# desk_winder.net
KiCad netlist of a schematic drawn in EAGLE
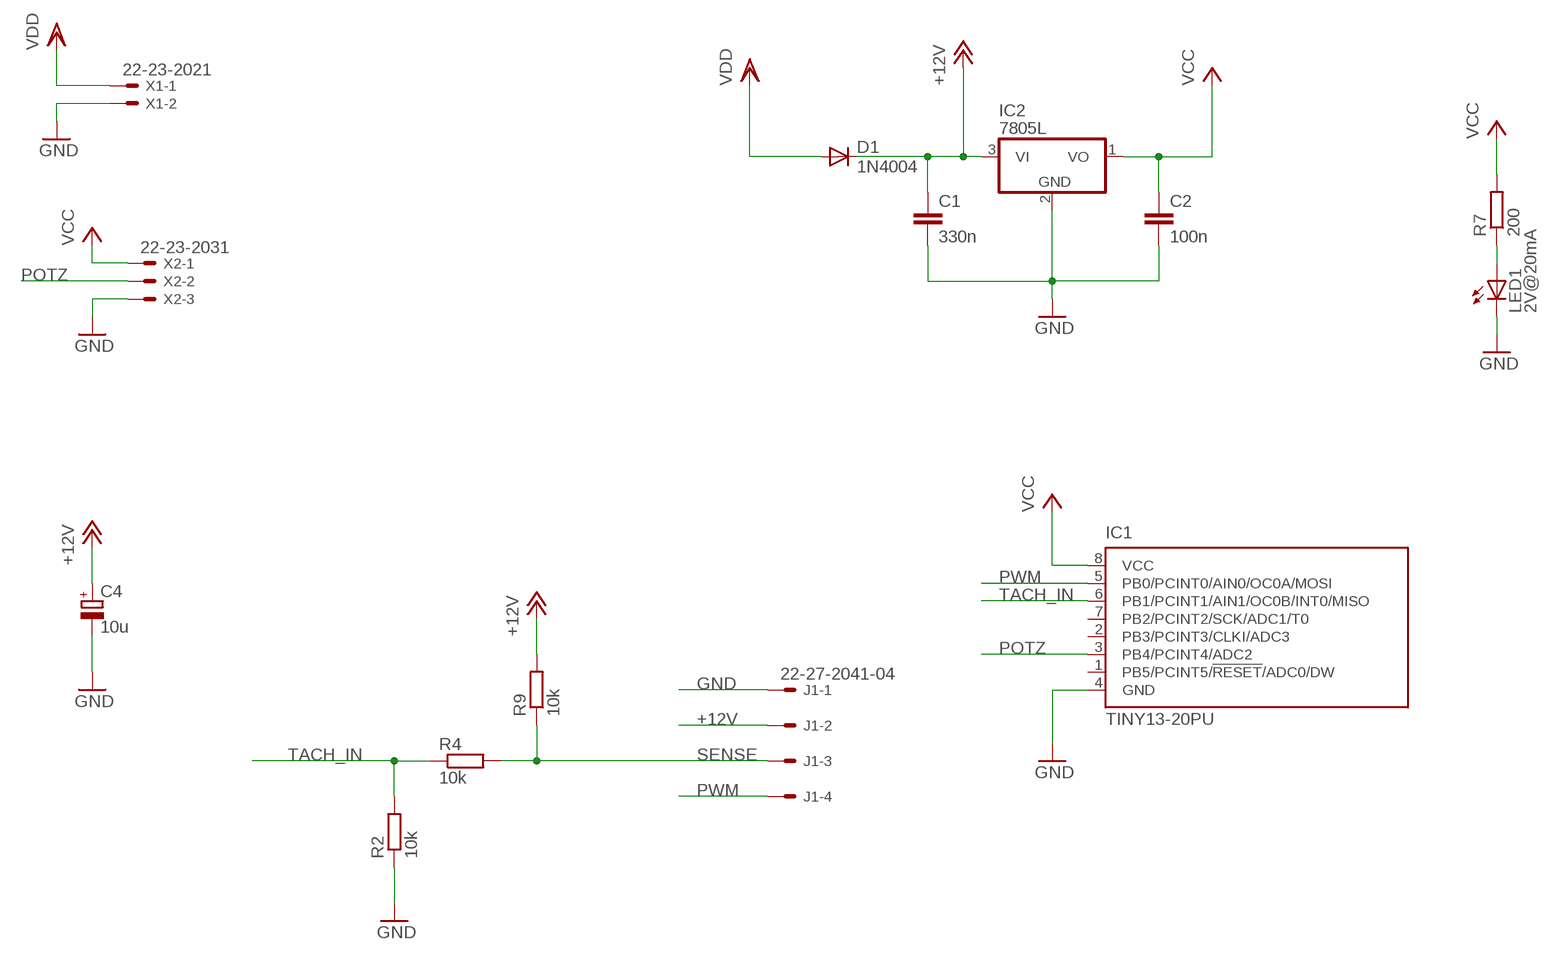
[diagram p0: schematic, sheet 1]

(export (version "E")
  (design (tool "Eeschema 10.0.6"))
  (components
    (comp (ref "C1")
      (value "330n")
      (footprint "eagle-import:C050-025X075")
      (libsource (lib "eagle-import") (part "C-EU050-025X075"))
    )
    (comp (ref "C2")
      (value "100n")
      (footprint "eagle-import:C050-025X075")
      (libsource (lib "eagle-import") (part "C-EU050-025X075"))
    )
    (comp (ref "C4")
      (value "10u")
      (footprint "eagle-import:E2,5-6")
      (libsource (lib "eagle-import") (part "CPOL-EUE2.5-6"))
    )
    (comp (ref "D1")
      (value "1N4004")
      (footprint "eagle-import:DO41-10")
      (libsource (lib "eagle-import") (part "1N4004"))
    )
    (comp (ref "IC1")
      (value "TINY13-20PU")
      (footprint "eagle-import:DIL08")
      (fields (field (name "MPN") "ATTINY13-20PU"))
      (libsource (lib "eagle-import") (part "TINY13PU-20"))
    )
    (comp (ref "IC2")
      (value "7805L")
      (footprint "eagle-import:TO92")
      (libsource (lib "eagle-import") (part "78L05"))
    )
    (comp (ref "J1")
      (value "22-27-2041-04")
      (footprint "eagle-import:6410-04")
      (libsource (lib "eagle-import") (part "22-?-0427-2041"))
    )
    (comp (ref "LED1")
      (value "2V@20mA")
      (footprint "eagle-import:LED5MM")
      (libsource (lib "eagle-import") (part "LED5MM"))
    )
    (comp (ref "R2")
      (value "10k")
      (footprint "eagle-import:0207_12")
      (libsource (lib "eagle-import") (part "R-EU_0207/12"))
    )
    (comp (ref "R4")
      (value "10k")
      (footprint "eagle-import:0207_12")
      (libsource (lib "eagle-import") (part "R-EU_0207/12"))
    )
    (comp (ref "R7")
      (value "200")
      (footprint "eagle-import:0207_12")
      (libsource (lib "eagle-import") (part "R-EU_0207/12"))
    )
    (comp (ref "R9")
      (value "10k")
      (footprint "eagle-import:0207_12")
      (libsource (lib "eagle-import") (part "R-EU_0207/12"))
    )
    (comp (ref "X1")
      (value "22-23-2021")
      (footprint "eagle-import:22-23-2021")
      (fields (field (name "MF") "MOLEX"))
      (libsource (lib "eagle-import") (part "22-23-2021"))
    )
    (comp (ref "X2")
      (value "22-23-2031")
      (footprint "eagle-import:22-23-2031")
      (fields (field (name "MF") "MOLEX"))
      (libsource (lib "eagle-import") (part "22-23-2031"))
    )
  )
  (nets
    (net (code "1") (name "+12V") (class "Default")
      (node (ref "C1") (pin "1") (pinfunction "1_1") (pintype "passive"))
      (node (ref "C4") (pin "+") (pinfunction "+_+") (pintype "passive"))
      (node (ref "D1") (pin "C") (pinfunction "C_C") (pintype "passive"))
      (node (ref "IC2") (pin "3") (pinfunction "VI_3") (pintype "input"))
      (node (ref "J1") (pin "2") (pinfunction "S_2") (pintype "passive"))
      (node (ref "R9") (pin "2") (pinfunction "2_2") (pintype "passive"))
    )
    (net (code "2") (name "/POTZ") (class "Default")
      (node (ref "IC1") (pin "3") (pinfunction "PB4/PCINT4/ADC2_3") (pintype "bidirectional"))
      (node (ref "X2") (pin "2") (pinfunction "S_2") (pintype "passive"))
    )
    (net (code "3") (name "/PWM") (class "Default")
      (node (ref "IC1") (pin "5") (pinfunction "PB0/PCINT0/AIN0/OC0A/MOSI_5") (pintype "bidirectional"))
      (node (ref "J1") (pin "4") (pinfunction "S_4") (pintype "passive"))
    )
    (net (code "4") (name "/SENSE") (class "Default")
      (node (ref "J1") (pin "3") (pinfunction "S_3") (pintype "passive"))
      (node (ref "R4") (pin "2") (pinfunction "2_2") (pintype "passive"))
      (node (ref "R9") (pin "1") (pinfunction "1_1") (pintype "passive"))
    )
    (net (code "5") (name "/TACH_IN") (class "Default")
      (node (ref "IC1") (pin "6") (pinfunction "PB1/PCINT1/AIN1/OC0B/INT0/MISO_6") (pintype "bidirectional"))
      (node (ref "R2") (pin "2") (pinfunction "2_2") (pintype "passive"))
      (node (ref "R4") (pin "1") (pinfunction "1_1") (pintype "passive"))
    )
    (net (code "6") (name "GND") (class "Default")
      (node (ref "C1") (pin "2") (pinfunction "2_2") (pintype "passive"))
      (node (ref "C2") (pin "2") (pinfunction "2_2") (pintype "passive"))
      (node (ref "C4") (pin "-") (pinfunction "-_-") (pintype "passive"))
      (node (ref "IC1") (pin "4") (pinfunction "GND_4") (pintype "power_in"))
      (node (ref "IC2") (pin "2") (pinfunction "GND_2") (pintype "passive"))
      (node (ref "J1") (pin "1") (pinfunction "S_1") (pintype "passive"))
      (node (ref "LED1") (pin "K") (pinfunction "C_K") (pintype "passive"))
      (node (ref "R2") (pin "1") (pinfunction "1_1") (pintype "passive"))
      (node (ref "X1") (pin "2") (pinfunction "S_2") (pintype "passive"))
      (node (ref "X2") (pin "3") (pinfunction "S_3") (pintype "passive"))
    )
    (net (code "7") (name "Net-(LED1-PadA)") (class "Default")
      (node (ref "LED1") (pin "A") (pinfunction "A_A") (pintype "passive"))
      (node (ref "R7") (pin "1") (pinfunction "1_1") (pintype "passive"))
    )
    (net (code "8") (name "VCC") (class "Default")
      (node (ref "C2") (pin "1") (pinfunction "1_1") (pintype "passive"))
      (node (ref "IC1") (pin "8") (pinfunction "VCC_8") (pintype "power_in"))
      (node (ref "IC2") (pin "1") (pinfunction "VO_1") (pintype "passive"))
      (node (ref "R7") (pin "2") (pinfunction "2_2") (pintype "passive"))
      (node (ref "X2") (pin "1") (pinfunction "S_1") (pintype "passive"))
    )
    (net (code "9") (name "VDD") (class "Default")
      (node (ref "D1") (pin "A") (pinfunction "A_A") (pintype "passive"))
      (node (ref "X1") (pin "1") (pinfunction "S_1") (pintype "passive"))
    )
    (net (code "10") (name "unconnected-(IC1-PB2{slash}PCINT2{slash}SCK{slash}ADC1{slash}T0-Pad7)") (class "Default")
      (node (ref "IC1") (pin "7") (pinfunction "PB2/PCINT2/SCK/ADC1/T0_7") (pintype "bidirectional"))
    )
    (net (code "11") (name "unconnected-(IC1-PB3{slash}PCINT3{slash}CLKI{slash}ADC3-Pad2)") (class "Default")
      (node (ref "IC1") (pin "2") (pinfunction "PB3/PCINT3/CLKI/ADC3_2") (pintype "bidirectional"))
    )
    (net (code "12") (name "unconnected-(IC1-PB5{slash}PCINT5{slash}~{RESET}{slash}ADC0{slash}DW-Pad1)") (class "Default")
      (node (ref "IC1") (pin "1") (pinfunction "PB5/PCINT5/~{RESET}/ADC0/DW_1") (pintype "bidirectional"))
    )
  )
)
